# AA8513.net
KiCad netlist of a schematic drawn in Altium Designer
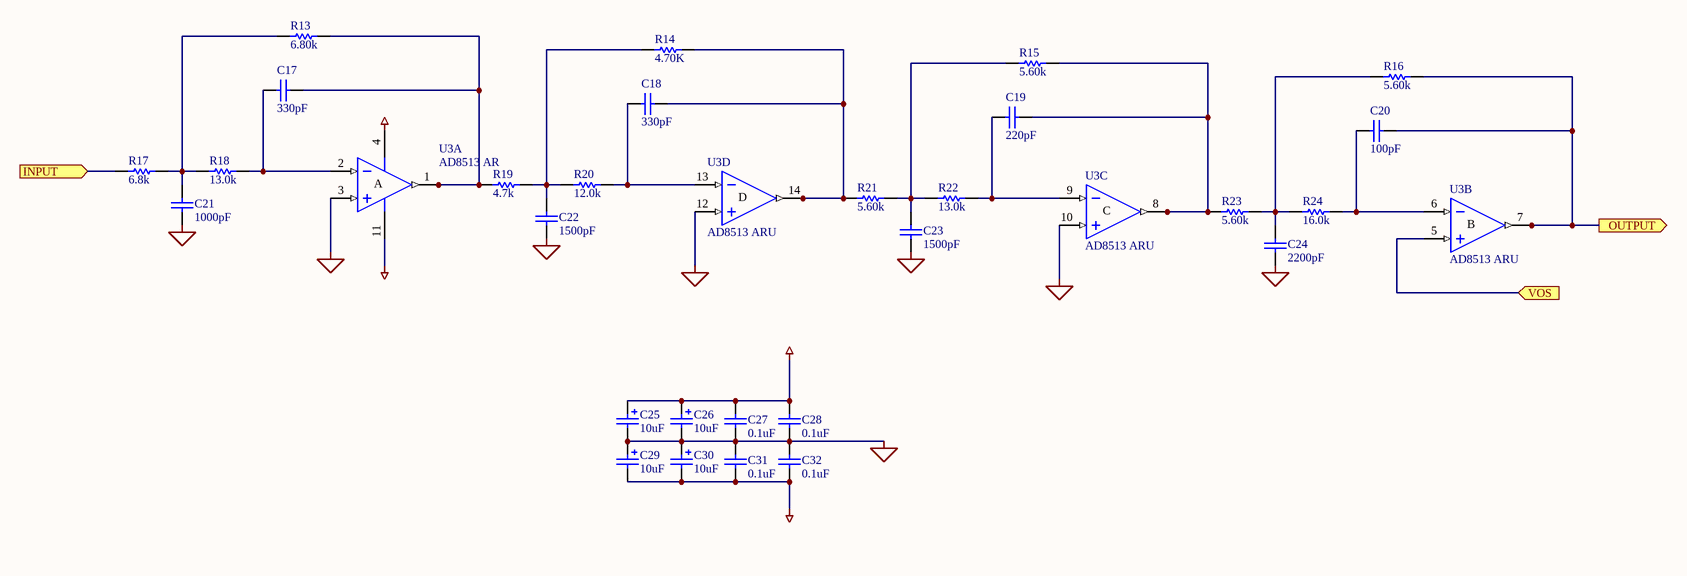
[diagram p0: AA8513.SCHDOC]

(export (version "E")
  (design (tool "Eeschema 10.0.6"))
  (components
    (comp (ref "C17")
      (value "330pF")
      (footprint "CC1608-0603")
      (description "Capacitor")
      (fields
        (field (name "MANUFACTURER") "Generic Components")
        (field (name "Comment") "Cap")
        (field (name "PUBLISHER") "Altium Limited")
      )
      (libsource (lib "Miscellaneous Devices") (part "Cap"))
    )
    (comp (ref "C18")
      (value "330pF")
      (footprint "CC1608-0603")
      (description "Capacitor")
      (fields
        (field (name "MANUFACTURER") "Generic Components")
        (field (name "Comment") "Cap")
        (field (name "PUBLISHER") "Altium Limited")
      )
      (libsource (lib "Miscellaneous Devices") (part "Cap"))
    )
    (comp (ref "C19")
      (value "220pF")
      (footprint "CC1608-0603")
      (description "Capacitor")
      (fields
        (field (name "MANUFACTURER") "Generic Components")
        (field (name "Comment") "Cap")
        (field (name "PUBLISHER") "Altium Limited")
      )
      (libsource (lib "Miscellaneous Devices") (part "Cap"))
    )
    (comp (ref "C20")
      (value "100pF")
      (footprint "CC1608-0603")
      (description "Capacitor")
      (fields
        (field (name "MANUFACTURER") "Generic Components")
        (field (name "Comment") "Cap")
        (field (name "PUBLISHER") "Altium Limited")
      )
      (libsource (lib "Miscellaneous Devices") (part "Cap"))
    )
    (comp (ref "C21")
      (value "1000pF")
      (footprint "CC1608-0603")
      (description "Capacitor")
      (fields
        (field (name "MANUFACTURER") "Generic Components")
        (field (name "Comment") "Cap")
        (field (name "PUBLISHER") "Altium Limited")
      )
      (libsource (lib "Miscellaneous Devices") (part "Cap"))
    )
    (comp (ref "C22")
      (value "1500pF")
      (footprint "CC1608-0603")
      (description "Capacitor")
      (fields
        (field (name "MANUFACTURER") "Generic Components")
        (field (name "Comment") "Cap")
        (field (name "PUBLISHER") "Altium Limited")
      )
      (libsource (lib "Miscellaneous Devices") (part "Cap"))
    )
    (comp (ref "C23")
      (value "1500pF")
      (footprint "CC1608-0603")
      (description "Capacitor")
      (fields
        (field (name "MANUFACTURER") "Generic Components")
        (field (name "Comment") "Cap")
        (field (name "PUBLISHER") "Altium Limited")
      )
      (libsource (lib "Miscellaneous Devices") (part "Cap"))
    )
    (comp (ref "C24")
      (value "2200pF")
      (footprint "CC1608-0603")
      (description "Capacitor")
      (fields
        (field (name "MANUFACTURER") "Generic Components")
        (field (name "Comment") "Cap")
        (field (name "PUBLISHER") "Altium Limited")
      )
      (libsource (lib "Miscellaneous Devices") (part "Cap"))
    )
    (comp (ref "C25")
      (value "10uF")
      (footprint "TC3528-1411")
      (description "Polarized Capacitor (Radial)")
      (fields
        (field (name "MANUFACTURER") "Generic Components")
        (field (name "Comment") "Cap Pol1")
        (field (name "PUBLISHER") "Altium Limited")
      )
      (libsource (lib "Miscellaneous Devices") (part "Cap Pol1"))
    )
    (comp (ref "C26")
      (value "10uF")
      (footprint "TC3528-1411")
      (description "Polarized Capacitor (Radial)")
      (fields
        (field (name "MANUFACTURER") "Generic Components")
        (field (name "Comment") "Cap Pol1")
        (field (name "PUBLISHER") "Altium Limited")
      )
      (libsource (lib "Miscellaneous Devices") (part "Cap Pol1"))
    )
    (comp (ref "C27")
      (value "0.1uF")
      (footprint "CC1608-0603")
      (description "Capacitor")
      (fields
        (field (name "MANUFACTURER") "Generic Components")
        (field (name "Comment") "Cap")
        (field (name "PUBLISHER") "Altium Limited")
      )
      (libsource (lib "Miscellaneous Devices") (part "Cap"))
    )
    (comp (ref "C28")
      (value "0.1uF")
      (footprint "CC1608-0603")
      (description "Capacitor")
      (fields
        (field (name "MANUFACTURER") "Generic Components")
        (field (name "Comment") "Cap")
        (field (name "PUBLISHER") "Altium Limited")
      )
      (libsource (lib "Miscellaneous Devices") (part "Cap"))
    )
    (comp (ref "C29")
      (value "10uF")
      (footprint "TC3528-1411")
      (description "Polarized Capacitor (Radial)")
      (fields
        (field (name "MANUFACTURER") "Generic Components")
        (field (name "Comment") "Cap Pol1")
        (field (name "PUBLISHER") "Altium Limited")
      )
      (libsource (lib "Miscellaneous Devices") (part "Cap Pol1"))
    )
    (comp (ref "C30")
      (value "10uF")
      (footprint "TC3528-1411")
      (description "Polarized Capacitor (Radial)")
      (fields
        (field (name "MANUFACTURER") "Generic Components")
        (field (name "Comment") "Cap Pol1")
        (field (name "PUBLISHER") "Altium Limited")
      )
      (libsource (lib "Miscellaneous Devices") (part "Cap Pol1"))
    )
    (comp (ref "C31")
      (value "0.1uF")
      (footprint "CC1608-0603")
      (description "Capacitor")
      (fields
        (field (name "MANUFACTURER") "Generic Components")
        (field (name "Comment") "Cap")
        (field (name "PUBLISHER") "Altium Limited")
      )
      (libsource (lib "Miscellaneous Devices") (part "Cap"))
    )
    (comp (ref "C32")
      (value "0.1uF")
      (footprint "CC1608-0603")
      (description "Capacitor")
      (fields
        (field (name "MANUFACTURER") "Generic Components")
        (field (name "Comment") "Cap")
        (field (name "PUBLISHER") "Altium Limited")
      )
      (libsource (lib "Miscellaneous Devices") (part "Cap"))
    )
    (comp (ref "R13")
      (value "6.80k")
      (footprint "CC1608-0603")
      (description "Resistor")
      (fields
        (field (name "MANUFACTURER") "Generic Components")
        (field (name "Comment") "Res1")
        (field (name "PUBLISHER") "Altium Limited")
      )
      (libsource (lib "Miscellaneous Devices") (part "Res1"))
    )
    (comp (ref "R14")
      (value "4.70K")
      (footprint "CC1608-0603")
      (description "Resistor")
      (fields
        (field (name "MANUFACTURER") "Generic Components")
        (field (name "Comment") "Res1")
        (field (name "PUBLISHER") "Altium Limited")
      )
      (libsource (lib "Miscellaneous Devices") (part "Res1"))
    )
    (comp (ref "R15")
      (value "5.60k")
      (footprint "CC1608-0603")
      (description "Resistor")
      (fields
        (field (name "MANUFACTURER") "Generic Components")
        (field (name "Comment") "Res1")
        (field (name "PUBLISHER") "Altium Limited")
      )
      (libsource (lib "Miscellaneous Devices") (part "Res1"))
    )
    (comp (ref "R16")
      (value "5.60k")
      (footprint "CC1608-0603")
      (description "Resistor")
      (fields
        (field (name "MANUFACTURER") "Generic Components")
        (field (name "Comment") "Res1")
        (field (name "PUBLISHER") "Altium Limited")
      )
      (libsource (lib "Miscellaneous Devices") (part "Res1"))
    )
    (comp (ref "R17")
      (value "6.8k")
      (footprint "CC1608-0603")
      (description "Resistor")
      (fields
        (field (name "MANUFACTURER") "Generic Components")
        (field (name "Comment") "Res1")
        (field (name "PUBLISHER") "Altium Limited")
      )
      (libsource (lib "Miscellaneous Devices") (part "Res1"))
    )
    (comp (ref "R18")
      (value "13.0k")
      (footprint "CC1608-0603")
      (description "Resistor")
      (fields
        (field (name "MANUFACTURER") "Generic Components")
        (field (name "Comment") "Res1")
        (field (name "PUBLISHER") "Altium Limited")
      )
      (libsource (lib "Miscellaneous Devices") (part "Res1"))
    )
    (comp (ref "R19")
      (value "4.7k")
      (footprint "CC1608-0603")
      (description "Resistor")
      (fields
        (field (name "MANUFACTURER") "Generic Components")
        (field (name "Comment") "Res1")
        (field (name "PUBLISHER") "Altium Limited")
      )
      (libsource (lib "Miscellaneous Devices") (part "Res1"))
    )
    (comp (ref "R20")
      (value "12.0k")
      (footprint "CC1608-0603")
      (description "Resistor")
      (fields
        (field (name "MANUFACTURER") "Generic Components")
        (field (name "Comment") "Res1")
        (field (name "PUBLISHER") "Altium Limited")
      )
      (libsource (lib "Miscellaneous Devices") (part "Res1"))
    )
    (comp (ref "R21")
      (value "5.60k")
      (footprint "CC1608-0603")
      (description "Resistor")
      (fields
        (field (name "MANUFACTURER") "Generic Components")
        (field (name "Comment") "Res1")
        (field (name "PUBLISHER") "Altium Limited")
      )
      (libsource (lib "Miscellaneous Devices") (part "Res1"))
    )
    (comp (ref "R22")
      (value "13.0k")
      (footprint "CC1608-0603")
      (description "Resistor")
      (fields
        (field (name "MANUFACTURER") "Generic Components")
        (field (name "Comment") "Res1")
        (field (name "PUBLISHER") "Altium Limited")
      )
      (libsource (lib "Miscellaneous Devices") (part "Res1"))
    )
    (comp (ref "R23")
      (value "5.60k")
      (footprint "CC1608-0603")
      (description "Resistor")
      (fields
        (field (name "MANUFACTURER") "Generic Components")
        (field (name "Comment") "Res1")
        (field (name "PUBLISHER") "Altium Limited")
      )
      (libsource (lib "Miscellaneous Devices") (part "Res1"))
    )
    (comp (ref "R24")
      (value "16.0k")
      (footprint "CC1608-0603")
      (description "Resistor")
      (fields
        (field (name "MANUFACTURER") "Generic Components")
        (field (name "Comment") "Res1")
        (field (name "PUBLISHER") "Altium Limited")
      )
      (libsource (lib "Miscellaneous Devices") (part "Res1"))
    )
    (comp (ref "U3")
      (value "AD8513 AR")
      (footprint "SO-G14")
      (description "low-noise JFET quad OA")
      (libsource (lib "My devices") (part "AD8513ARU"))
    )
  )
  (nets
    (net (code "1") (name "/INPUT") (class "Default")
      (node (ref "R17") (pin "1") (pinfunction "1_1") (pintype "passive"))
    )
    (net (code "2") (name "/OUTPUT") (class "Default")
      (node (ref "C20") (pin "1") (pinfunction "1_1") (pintype "passive"))
      (node (ref "R16") (pin "1") (pinfunction "1_1") (pintype "passive"))
      (node (ref "U3") (pin "7") (pinfunction "OUTB_7") (pintype "output"))
    )
    (net (code "3") (name "/VOS") (class "Default")
      (node (ref "U3") (pin "5") (pinfunction "IN+B_5") (pintype "input"))
    )
    (net (code "4") (name "AGND") (class "Default")
      (node (ref "C21") (pin "1") (pinfunction "1_1") (pintype "passive"))
      (node (ref "C22") (pin "1") (pinfunction "1_1") (pintype "passive"))
      (node (ref "C23") (pin "1") (pinfunction "1_1") (pintype "passive"))
      (node (ref "C24") (pin "1") (pinfunction "1_1") (pintype "passive"))
      (node (ref "C25") (pin "2") (pinfunction "2_2") (pintype "passive"))
      (node (ref "C26") (pin "2") (pinfunction "2_2") (pintype "passive"))
      (node (ref "C27") (pin "1") (pinfunction "1_1") (pintype "passive"))
      (node (ref "C28") (pin "1") (pinfunction "1_1") (pintype "passive"))
      (node (ref "C29") (pin "1") (pinfunction "1_1") (pintype "passive"))
      (node (ref "C30") (pin "1") (pinfunction "1_1") (pintype "passive"))
      (node (ref "C31") (pin "2") (pinfunction "2_2") (pintype "passive"))
      (node (ref "C32") (pin "2") (pinfunction "2_2") (pintype "passive"))
      (node (ref "U3") (pin "10") (pinfunction "IN+C_10") (pintype "input"))
      (node (ref "U3") (pin "12") (pinfunction "IN+D_12") (pintype "input"))
      (node (ref "U3") (pin "3") (pinfunction "IN+A_3") (pintype "input"))
    )
    (net (code "5") (name "AVDD") (class "Default")
      (node (ref "C25") (pin "1") (pinfunction "1_1") (pintype "passive"))
      (node (ref "C26") (pin "1") (pinfunction "1_1") (pintype "passive"))
      (node (ref "C27") (pin "2") (pinfunction "2_2") (pintype "passive"))
      (node (ref "C28") (pin "2") (pinfunction "2_2") (pintype "passive"))
      (node (ref "U3") (pin "4") (pinfunction "V+_4") (pintype "power_in"))
    )
    (net (code "6") (name "AVSS") (class "Default")
      (node (ref "C29") (pin "2") (pinfunction "2_2") (pintype "passive"))
      (node (ref "C30") (pin "2") (pinfunction "2_2") (pintype "passive"))
      (node (ref "C31") (pin "1") (pinfunction "1_1") (pintype "passive"))
      (node (ref "C32") (pin "1") (pinfunction "1_1") (pintype "passive"))
      (node (ref "U3") (pin "11") (pinfunction "V-_11") (pintype "power_in"))
    )
    (net (code "7") (name "Net-(C21-Pad2)") (class "Default")
      (node (ref "C21") (pin "2") (pinfunction "2_2") (pintype "passive"))
      (node (ref "R13") (pin "2") (pinfunction "2_2") (pintype "passive"))
      (node (ref "R17") (pin "2") (pinfunction "2_2") (pintype "passive"))
      (node (ref "R18") (pin "1") (pinfunction "1_1") (pintype "passive"))
    )
    (net (code "8") (name "Net-(C22-Pad2)") (class "Default")
      (node (ref "C22") (pin "2") (pinfunction "2_2") (pintype "passive"))
      (node (ref "R14") (pin "2") (pinfunction "2_2") (pintype "passive"))
      (node (ref "R19") (pin "2") (pinfunction "2_2") (pintype "passive"))
      (node (ref "R20") (pin "1") (pinfunction "1_1") (pintype "passive"))
    )
    (net (code "9") (name "Net-(C23-Pad2)") (class "Default")
      (node (ref "C23") (pin "2") (pinfunction "2_2") (pintype "passive"))
      (node (ref "R15") (pin "2") (pinfunction "2_2") (pintype "passive"))
      (node (ref "R21") (pin "2") (pinfunction "2_2") (pintype "passive"))
      (node (ref "R22") (pin "1") (pinfunction "1_1") (pintype "passive"))
    )
    (net (code "10") (name "Net-(C24-Pad2)") (class "Default")
      (node (ref "C24") (pin "2") (pinfunction "2_2") (pintype "passive"))
      (node (ref "R16") (pin "2") (pinfunction "2_2") (pintype "passive"))
      (node (ref "R23") (pin "2") (pinfunction "2_2") (pintype "passive"))
      (node (ref "R24") (pin "1") (pinfunction "1_1") (pintype "passive"))
    )
    (net (code "11") (name "Net-(U3A-IN-A)") (class "Default")
      (node (ref "C17") (pin "2") (pinfunction "2_2") (pintype "passive"))
      (node (ref "R18") (pin "2") (pinfunction "2_2") (pintype "passive"))
      (node (ref "U3") (pin "2") (pinfunction "IN-A_2") (pintype "input"))
    )
    (net (code "12") (name "Net-(U3A-OUTA)") (class "Default")
      (node (ref "C17") (pin "1") (pinfunction "1_1") (pintype "passive"))
      (node (ref "R13") (pin "1") (pinfunction "1_1") (pintype "passive"))
      (node (ref "R19") (pin "1") (pinfunction "1_1") (pintype "passive"))
      (node (ref "U3") (pin "1") (pinfunction "OUTA_1") (pintype "output"))
    )
    (net (code "13") (name "Net-(U3B-IN-B)") (class "Default")
      (node (ref "C20") (pin "2") (pinfunction "2_2") (pintype "passive"))
      (node (ref "R24") (pin "2") (pinfunction "2_2") (pintype "passive"))
      (node (ref "U3") (pin "6") (pinfunction "IN-B_6") (pintype "input"))
    )
    (net (code "14") (name "Net-(U3C-IN-C)") (class "Default")
      (node (ref "C19") (pin "2") (pinfunction "2_2") (pintype "passive"))
      (node (ref "R22") (pin "2") (pinfunction "2_2") (pintype "passive"))
      (node (ref "U3") (pin "9") (pinfunction "IN-C_9") (pintype "input"))
    )
    (net (code "15") (name "Net-(U3C-OUTC)") (class "Default")
      (node (ref "C19") (pin "1") (pinfunction "1_1") (pintype "passive"))
      (node (ref "R15") (pin "1") (pinfunction "1_1") (pintype "passive"))
      (node (ref "R23") (pin "1") (pinfunction "1_1") (pintype "passive"))
      (node (ref "U3") (pin "8") (pinfunction "OUTC_8") (pintype "output"))
    )
    (net (code "16") (name "Net-(U3D-IN-D)") (class "Default")
      (node (ref "C18") (pin "2") (pinfunction "2_2") (pintype "passive"))
      (node (ref "R20") (pin "2") (pinfunction "2_2") (pintype "passive"))
      (node (ref "U3") (pin "13") (pinfunction "IN-D_13") (pintype "input"))
    )
    (net (code "17") (name "Net-(U3D-OUTD)") (class "Default")
      (node (ref "C18") (pin "1") (pinfunction "1_1") (pintype "passive"))
      (node (ref "R14") (pin "1") (pinfunction "1_1") (pintype "passive"))
      (node (ref "R21") (pin "1") (pinfunction "1_1") (pintype "passive"))
      (node (ref "U3") (pin "14") (pinfunction "OUTD_14") (pintype "output"))
    )
  )
)
